# ADC.net
KiCad netlist of a schematic drawn in Altium Designer
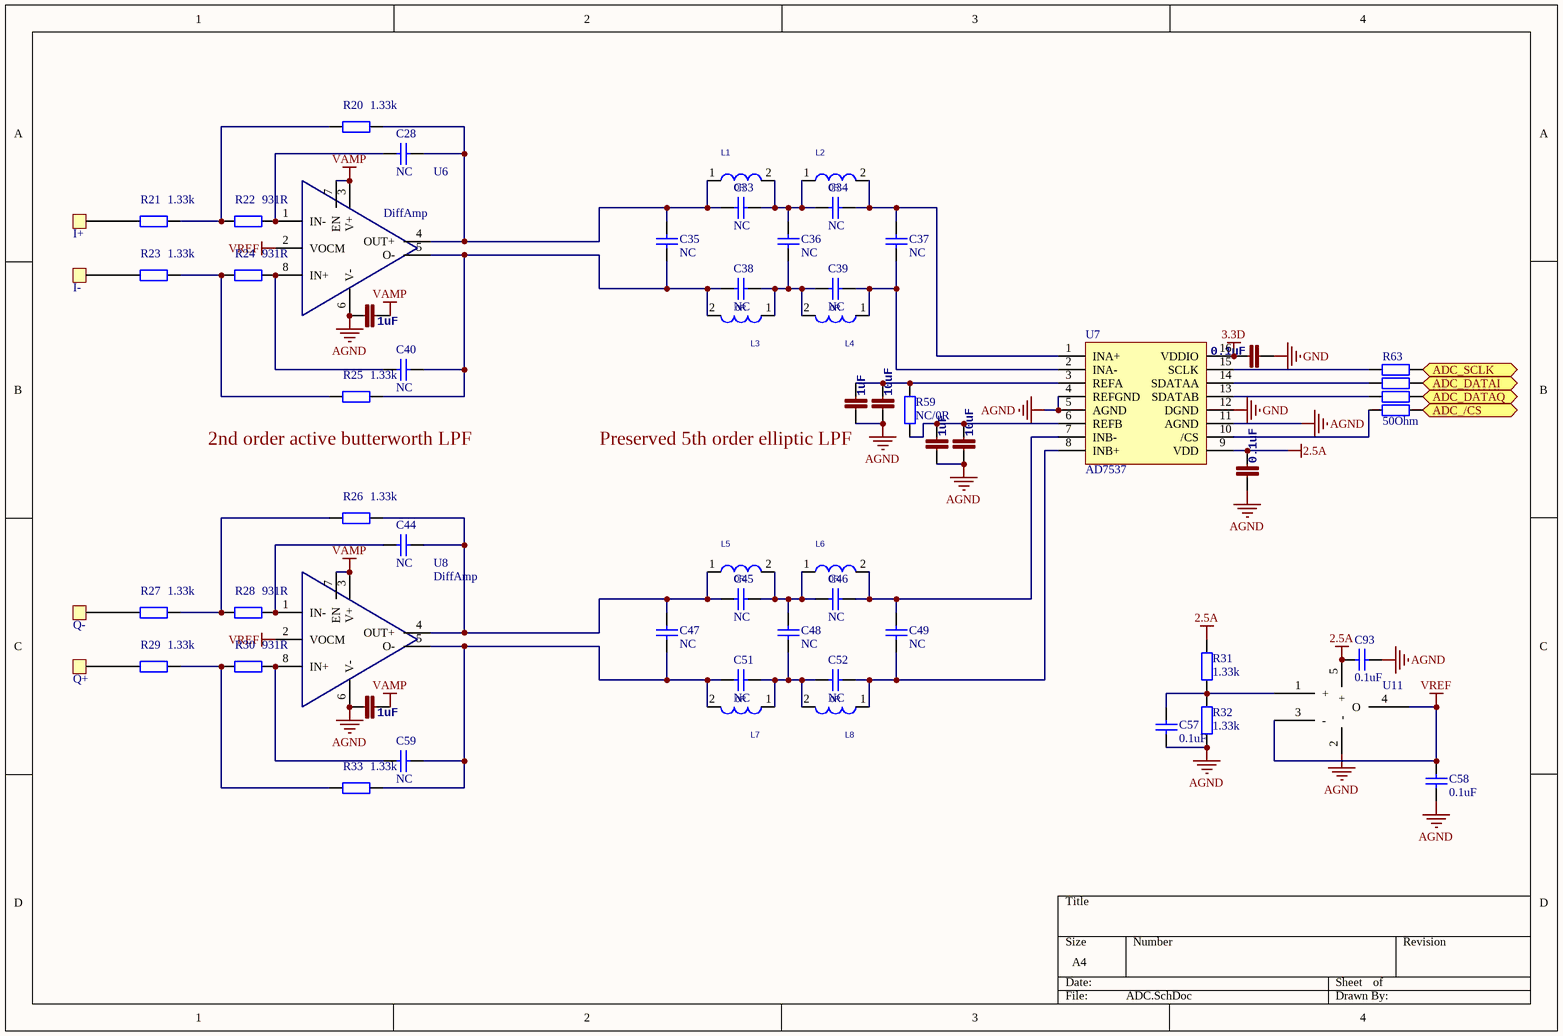
[diagram p0: ADC.SchDoc]

(export (version "E")
  (design (tool "Eeschema 10.0.6"))
  (components
    (comp (ref "C28")
      (value "NC")
      (footprint "0402")
      (description "Capacitor")
      (fields (field (name "PUBLISHER") "Altium Limited"))
      (libsource (lib "RTC6705") (part "Cap"))
    )
    (comp (ref "C29")
      (value "0.1uF")
      (footprint "0402")
      (description "<b>Capacitor</b>\nStandard 0603 ceramic capacitor, and 0.1\" leaded capacitor.")
      (fields (field (name "PARTNO") "CC0402ZRY5V7BB104"))
      (libsource (lib "") (part "CAP0402-CAP_2"))
    )
    (comp (ref "C30")
      (value "0.1uF")
      (footprint "0603")
      (description "<b>Capacitor</b>\nStandard 0603 ceramic capacitor, and 0.1\" leaded capacitor.")
      (fields (field (name "PARTNO") "CC0402ZRY5V7BB104"))
      (libsource (lib "pixhawk2") (part "CAP0402-CAP"))
    )
    (comp (ref "C31")
      (value "10uF")
      (footprint "0603")
      (description "<b>Capacitor</b>\nStandard 0603 ceramic capacitor, and 0.1\" leaded capacitor.")
      (fields (field (name "PARTNO") "CC0402ZRY5V7BB104"))
      (libsource (lib "pixhawk2") (part "CAP0402-CAP"))
    )
    (comp (ref "C32")
      (value "1uF")
      (footprint "0805")
      (description "<b>Capacitor</b>\nStandard 0603 ceramic capacitor, and 0.1\" leaded capacitor.")
      (fields (field (name "PARTNO") "CC0402ZRY5V7BB104"))
      (libsource (lib "pixhawk2") (part "CAP0402-CAP"))
    )
    (comp (ref "C33")
      (value "NC")
      (footprint "0402")
      (description "Capacitor")
      (fields (field (name "PUBLISHER") "Altium Limited"))
      (libsource (lib "RTC6705") (part "Cap"))
    )
    (comp (ref "C34")
      (value "NC")
      (footprint "0402")
      (description "Capacitor")
      (fields (field (name "PUBLISHER") "Altium Limited"))
      (libsource (lib "RTC6705") (part "Cap"))
    )
    (comp (ref "C35")
      (value "NC")
      (footprint "0402")
      (description "Capacitor")
      (fields (field (name "PUBLISHER") "Altium Limited"))
      (libsource (lib "RTC6705") (part "Cap"))
    )
    (comp (ref "C36")
      (value "NC")
      (footprint "0402")
      (description "Capacitor")
      (fields (field (name "PUBLISHER") "Altium Limited"))
      (libsource (lib "RTC6705") (part "Cap"))
    )
    (comp (ref "C37")
      (value "NC")
      (footprint "0402")
      (description "Capacitor")
      (fields (field (name "PUBLISHER") "Altium Limited"))
      (libsource (lib "RTC6705") (part "Cap"))
    )
    (comp (ref "C38")
      (value "NC")
      (footprint "0402")
      (description "Capacitor")
      (fields (field (name "PUBLISHER") "Altium Limited"))
      (libsource (lib "RTC6705") (part "Cap"))
    )
    (comp (ref "C39")
      (value "NC")
      (footprint "0402")
      (description "Capacitor")
      (fields (field (name "PUBLISHER") "Altium Limited"))
      (libsource (lib "RTC6705") (part "Cap"))
    )
    (comp (ref "C40")
      (value "NC")
      (footprint "0402")
      (description "Capacitor")
      (fields (field (name "PUBLISHER") "Altium Limited"))
      (libsource (lib "RTC6705") (part "Cap"))
    )
    (comp (ref "C41")
      (value "1uF")
      (footprint "0603")
      (description "<b>Capacitor</b>\nStandard 0603 ceramic capacitor, and 0.1\" leaded capacitor.")
      (fields (field (name "PARTNO") "CC0402ZRY5V7BB104"))
      (libsource (lib "pixhawk2") (part "CAP0402-CAP"))
    )
    (comp (ref "C43")
      (value "10uF")
      (footprint "0805")
      (description "<b>Capacitor</b>\nStandard 0603 ceramic capacitor, and 0.1\" leaded capacitor.")
      (fields (field (name "PARTNO") "CC0402ZRY5V7BB104"))
      (libsource (lib "pixhawk2") (part "CAP0402-CAP"))
    )
    (comp (ref "C44")
      (value "NC")
      (footprint "0402")
      (description "Capacitor")
      (fields (field (name "PUBLISHER") "Altium Limited"))
      (libsource (lib "RTC6705") (part "Cap"))
    )
    (comp (ref "C45")
      (value "NC")
      (footprint "0402")
      (description "Capacitor")
      (fields (field (name "PUBLISHER") "Altium Limited"))
      (libsource (lib "RTC6705") (part "Cap"))
    )
    (comp (ref "C46")
      (value "NC")
      (footprint "0402")
      (description "Capacitor")
      (fields (field (name "PUBLISHER") "Altium Limited"))
      (libsource (lib "RTC6705") (part "Cap"))
    )
    (comp (ref "C47")
      (value "NC")
      (footprint "0402")
      (description "Capacitor")
      (fields (field (name "PUBLISHER") "Altium Limited"))
      (libsource (lib "RTC6705") (part "Cap"))
    )
    (comp (ref "C48")
      (value "NC")
      (footprint "0402")
      (description "Capacitor")
      (fields (field (name "PUBLISHER") "Altium Limited"))
      (libsource (lib "RTC6705") (part "Cap"))
    )
    (comp (ref "C49")
      (value "NC")
      (footprint "0402")
      (description "Capacitor")
      (fields (field (name "PUBLISHER") "Altium Limited"))
      (libsource (lib "RTC6705") (part "Cap"))
    )
    (comp (ref "C51")
      (value "NC")
      (footprint "0402")
      (description "Capacitor")
      (fields (field (name "PUBLISHER") "Altium Limited"))
      (libsource (lib "RTC6705") (part "Cap"))
    )
    (comp (ref "C52")
      (value "NC")
      (footprint "0402")
      (description "Capacitor")
      (fields (field (name "PUBLISHER") "Altium Limited"))
      (libsource (lib "RTC6705") (part "Cap"))
    )
    (comp (ref "C57")
      (value "0.1uF")
      (footprint "0402")
      (description "Capacitor")
      (fields (field (name "PUBLISHER") "Altium Limited"))
      (libsource (lib "RTC6705") (part "Cap"))
    )
    (comp (ref "C58")
      (value "0.1uF")
      (footprint "0402")
      (description "Capacitor")
      (fields (field (name "PUBLISHER") "Altium Limited"))
      (libsource (lib "RTC6705") (part "Cap"))
    )
    (comp (ref "C59")
      (value "NC")
      (footprint "0402")
      (description "Capacitor")
      (fields (field (name "PUBLISHER") "Altium Limited"))
      (libsource (lib "RTC6705") (part "Cap"))
    )
    (comp (ref "C89")
      (value "1uF")
      (footprint "0603")
      (description "<b>Capacitor</b>\nStandard 0603 ceramic capacitor, and 0.1\" leaded capacitor.")
      (fields (field (name "PARTNO") "CC0402ZRY5V7BB104"))
      (libsource (lib "") (part "CAP0402-CAP_1"))
    )
    (comp (ref "C90")
      (value "1uF")
      (footprint "0603")
      (description "<b>Capacitor</b>\nStandard 0603 ceramic capacitor, and 0.1\" leaded capacitor.")
      (fields (field (name "PARTNO") "CC0402ZRY5V7BB104"))
      (libsource (lib "") (part "CAP0402-CAP_1"))
    )
    (comp (ref "C93")
      (value "0.1uF")
      (footprint "0402")
      (description "Capacitor")
      (fields (field (name "PUBLISHER") "Altium Limited"))
      (libsource (lib "RTC6705") (part "Cap"))
    )
    (comp (ref "I+") (value "TestPad") (footprint "TestPad - 1mm") (libsource (lib "sch") (part "TestPad")))
    (comp (ref "I-") (value "TestPad") (footprint "TestPad - 1mm") (libsource (lib "sch") (part "TestPad")))
    (comp (ref "L1") (value "0R") (footprint "0402") (libsource (lib "*") (part "L/2.5*2.0")))
    (comp (ref "L2") (value "0R") (footprint "0402") (libsource (lib "*") (part "L/2.5*2.0")))
    (comp (ref "L3") (value "0R") (footprint "0402") (libsource (lib "*") (part "L/2.5*2.0")))
    (comp (ref "L4") (value "0R") (footprint "0402") (libsource (lib "*") (part "L/2.5*2.0")))
    (comp (ref "L5") (value "0R") (footprint "0402") (libsource (lib "*") (part "L/2.5*2.0")))
    (comp (ref "L6") (value "0R") (footprint "0402") (libsource (lib "*") (part "L/2.5*2.0")))
    (comp (ref "L7") (value "0R") (footprint "0402") (libsource (lib "*") (part "L/2.5*2.0")))
    (comp (ref "L8") (value "0R") (footprint "0402") (libsource (lib "*") (part "L/2.5*2.0")))
    (comp (ref "Q+") (value "TestPad") (footprint "TestPad - 1mm") (libsource (lib "sch") (part "TestPad")))
    (comp (ref "Q-") (value "TestPad") (footprint "TestPad - 1mm") (libsource (lib "sch") (part "TestPad")))
    (comp (ref "R20")
      (value "1.33k")
      (footprint "0402")
      (description "Resistor")
      (fields (field (name "PUBLISHER") "Altium Limited"))
      (libsource (lib "Miscellaneous Devices") (part "Res2"))
    )
    (comp (ref "R21")
      (value "1.33k")
      (footprint "0402")
      (description "Resistor")
      (fields (field (name "PUBLISHER") "Altium Limited"))
      (libsource (lib "Miscellaneous Devices") (part "Res2"))
    )
    (comp (ref "R22")
      (value "931R")
      (footprint "0402")
      (description "Resistor")
      (fields (field (name "PUBLISHER") "Altium Limited"))
      (libsource (lib "Miscellaneous Devices") (part "Res2"))
    )
    (comp (ref "R23")
      (value "1.33k")
      (footprint "0402")
      (description "Resistor")
      (fields (field (name "PUBLISHER") "Altium Limited"))
      (libsource (lib "Miscellaneous Devices") (part "Res2"))
    )
    (comp (ref "R24")
      (value "931R")
      (footprint "0402")
      (description "Resistor")
      (fields (field (name "PUBLISHER") "Altium Limited"))
      (libsource (lib "Miscellaneous Devices") (part "Res2"))
    )
    (comp (ref "R25")
      (value "1.33k")
      (footprint "0402")
      (description "Resistor")
      (fields (field (name "PUBLISHER") "Altium Limited"))
      (libsource (lib "Miscellaneous Devices") (part "Res2"))
    )
    (comp (ref "R26")
      (value "1.33k")
      (footprint "0402")
      (description "Resistor")
      (fields (field (name "PUBLISHER") "Altium Limited"))
      (libsource (lib "Miscellaneous Devices") (part "Res2"))
    )
    (comp (ref "R27")
      (value "1.33k")
      (footprint "0402")
      (description "Resistor")
      (fields (field (name "PUBLISHER") "Altium Limited"))
      (libsource (lib "Miscellaneous Devices") (part "Res2"))
    )
    (comp (ref "R28")
      (value "931R")
      (footprint "0402")
      (description "Resistor")
      (fields (field (name "PUBLISHER") "Altium Limited"))
      (libsource (lib "Miscellaneous Devices") (part "Res2"))
    )
    (comp (ref "R29")
      (value "1.33k")
      (footprint "0402")
      (description "Resistor")
      (fields (field (name "PUBLISHER") "Altium Limited"))
      (libsource (lib "Miscellaneous Devices") (part "Res2"))
    )
    (comp (ref "R30")
      (value "931R")
      (footprint "0402")
      (description "Resistor")
      (fields (field (name "PUBLISHER") "Altium Limited"))
      (libsource (lib "Miscellaneous Devices") (part "Res2"))
    )
    (comp (ref "R31")
      (value "1.33k")
      (footprint "0402")
      (description "Resistor")
      (fields (field (name "PUBLISHER") "Altium Limited"))
      (libsource (lib "") (part "Res2_1"))
    )
    (comp (ref "R32")
      (value "1.33k")
      (footprint "0402")
      (description "Resistor")
      (fields (field (name "PUBLISHER") "Altium Limited"))
      (libsource (lib "") (part "Res2_1"))
    )
    (comp (ref "R33")
      (value "1.33k")
      (footprint "0402")
      (description "Resistor")
      (fields (field (name "PUBLISHER") "Altium Limited"))
      (libsource (lib "Miscellaneous Devices") (part "Res2"))
    )
    (comp (ref "R59")
      (value "NC/0R")
      (footprint "0402")
      (description "Resistor")
      (fields (field (name "PUBLISHER") "Altium Limited"))
      (libsource (lib "") (part "Res2_2"))
    )
    (comp (ref "R63")
      (value "50Ohm")
      (footprint "0402X4")
      (description "Resistor")
      (fields (field (name "Comment") "Res*4") (field (name "PUBLISHER") "Altium Limited"))
      (libsource (lib "sch") (part "Res*4"))
    )
    (comp (ref "U6") (value "DiffAmp") (footprint "MSOP8/VSSOP8") (libsource (lib "F4SDR") (part "DiffAmp")))
    (comp (ref "U7") (value "AD7537") (footprint "AD7357") (libsource (lib "F4SDR") (part "AD7537")))
    (comp (ref "U8") (value "DiffAmp") (footprint "MSOP8/VSSOP8") (libsource (lib "F4SDR") (part "DiffAmp")))
    (comp (ref "U11") (value "OP-SOT23") (footprint "SOT23-5") (libsource (lib "sch") (part "OP-SOT23")))
  )
  (nets
    (net (code "1") (name "/ADC_DATAI") (class "Default")
      (node (ref "R63") (pin "3") (pinfunction "3_3") (pintype "passive"))
    )
    (net (code "2") (name "/ADC_DATAQ") (class "Default")
      (node (ref "R63") (pin "2") (pinfunction "2_2") (pintype "passive"))
    )
    (net (code "3") (name "/ADC_SCLK") (class "Default")
      (node (ref "R63") (pin "4") (pinfunction "4_4") (pintype "passive"))
    )
    (net (code "4") (name "/ADC_{slash}CS") (class "Default")
      (node (ref "R63") (pin "1") (pinfunction "1_1") (pintype "passive"))
    )
    (net (code "5") (name "2.5A") (class "Default")
      (node (ref "C30") (pin "1") (pinfunction "1_1") (pintype "passive"))
      (node (ref "C93") (pin "1") (pinfunction "1_1") (pintype "passive"))
      (node (ref "R31") (pin "1") (pinfunction "1_1") (pintype "passive"))
      (node (ref "U11") (pin "5") (pinfunction "+_5") (pintype "passive"))
      (node (ref "U7") (pin "9") (pinfunction "VDD_9") (pintype "passive"))
    )
    (net (code "6") (name "3.3D") (class "Default")
      (node (ref "C29") (pin "1") (pinfunction "1_1") (pintype "passive"))
      (node (ref "U7") (pin "16") (pinfunction "VDDIO_16") (pintype "passive"))
    )
    (net (code "7") (name "AGND") (class "Default")
      (node (ref "C30") (pin "2") (pinfunction "2_2") (pintype "passive"))
      (node (ref "C31") (pin "2") (pinfunction "2_2") (pintype "passive"))
      (node (ref "C32") (pin "2") (pinfunction "2_2") (pintype "passive"))
      (node (ref "C41") (pin "2") (pinfunction "2_2") (pintype "passive"))
      (node (ref "C43") (pin "2") (pinfunction "2_2") (pintype "passive"))
      (node (ref "C57") (pin "2") (pinfunction "2_2") (pintype "passive"))
      (node (ref "C58") (pin "2") (pinfunction "2_2") (pintype "passive"))
      (node (ref "C89") (pin "2") (pinfunction "2_2") (pintype "passive"))
      (node (ref "C90") (pin "2") (pinfunction "2_2") (pintype "passive"))
      (node (ref "C93") (pin "2") (pinfunction "2_2") (pintype "passive"))
      (node (ref "R32") (pin "2") (pinfunction "2_2") (pintype "passive"))
      (node (ref "U11") (pin "2") (pinfunction "-_2") (pintype "passive"))
      (node (ref "U6") (pin "6") (pinfunction "V-_6") (pintype "passive"))
      (node (ref "U7") (pin "11") (pinfunction "AGND_11") (pintype "passive"))
      (node (ref "U7") (pin "4") (pinfunction "REFGND_4") (pintype "passive"))
      (node (ref "U7") (pin "5") (pinfunction "AGND_5") (pintype "passive"))
      (node (ref "U8") (pin "6") (pinfunction "V-_6") (pintype "passive"))
    )
    (net (code "8") (name "GND") (class "Default")
      (node (ref "C29") (pin "2") (pinfunction "2_2") (pintype "passive"))
      (node (ref "U7") (pin "12") (pinfunction "DGND_12") (pintype "passive"))
    )
    (net (code "9") (name "Net-(C33-Pad1)") (class "Default")
      (node (ref "C33") (pin "1") (pinfunction "1_1") (pintype "passive"))
      (node (ref "C34") (pin "2") (pinfunction "2_2") (pintype "passive"))
      (node (ref "C36") (pin "2") (pinfunction "2_2") (pintype "passive"))
      (node (ref "L1") (pin "2") (pinfunction "2_2") (pintype "passive"))
      (node (ref "L2") (pin "1") (pinfunction "1_1") (pintype "passive"))
    )
    (net (code "10") (name "Net-(C36-Pad1)") (class "Default")
      (node (ref "C36") (pin "1") (pinfunction "1_1") (pintype "passive"))
      (node (ref "C38") (pin "2") (pinfunction "2_2") (pintype "passive"))
      (node (ref "C39") (pin "1") (pinfunction "1_1") (pintype "passive"))
      (node (ref "L3") (pin "1") (pinfunction "1_1") (pintype "passive"))
      (node (ref "L4") (pin "2") (pinfunction "2_2") (pintype "passive"))
    )
    (net (code "11") (name "Net-(C45-Pad1)") (class "Default")
      (node (ref "C45") (pin "1") (pinfunction "1_1") (pintype "passive"))
      (node (ref "C46") (pin "2") (pinfunction "2_2") (pintype "passive"))
      (node (ref "C48") (pin "2") (pinfunction "2_2") (pintype "passive"))
      (node (ref "L5") (pin "2") (pinfunction "2_2") (pintype "passive"))
      (node (ref "L6") (pin "1") (pinfunction "1_1") (pintype "passive"))
    )
    (net (code "12") (name "Net-(C48-Pad1)") (class "Default")
      (node (ref "C48") (pin "1") (pinfunction "1_1") (pintype "passive"))
      (node (ref "C51") (pin "2") (pinfunction "2_2") (pintype "passive"))
      (node (ref "C52") (pin "1") (pinfunction "1_1") (pintype "passive"))
      (node (ref "L7") (pin "1") (pinfunction "1_1") (pintype "passive"))
      (node (ref "L8") (pin "2") (pinfunction "2_2") (pintype "passive"))
    )
    (net (code "13") (name "Net-(C57-Pad1)") (class "Default")
      (node (ref "C57") (pin "1") (pinfunction "1_1") (pintype "passive"))
      (node (ref "R31") (pin "2") (pinfunction "2_2") (pintype "passive"))
      (node (ref "R32") (pin "1") (pinfunction "1_1") (pintype "passive"))
      (node (ref "U11") (pin "1") (pinfunction "+_1") (pintype "passive"))
    )
    (net (code "14") (name "Net-(I+-3)") (class "Default")
      (node (ref "I+") (pin "1") (pinfunction "3_1") (pintype "passive"))
      (node (ref "R21") (pin "2") (pinfunction "2_2") (pintype "passive"))
    )
    (net (code "15") (name "Net-(I--3)") (class "Default")
      (node (ref "I-") (pin "1") (pinfunction "3_1") (pintype "passive"))
      (node (ref "R23") (pin "2") (pinfunction "2_2") (pintype "passive"))
    )
    (net (code "16") (name "Net-(Q+-3)") (class "Default")
      (node (ref "Q+") (pin "1") (pinfunction "3_1") (pintype "passive"))
      (node (ref "R29") (pin "2") (pinfunction "2_2") (pintype "passive"))
    )
    (net (code "17") (name "Net-(Q--3)") (class "Default")
      (node (ref "Q-") (pin "1") (pinfunction "3_1") (pintype "passive"))
      (node (ref "R27") (pin "2") (pinfunction "2_2") (pintype "passive"))
    )
    (net (code "18") (name "Net-(R20-Pad2)") (class "Default")
      (node (ref "R20") (pin "2") (pinfunction "2_2") (pintype "passive"))
      (node (ref "R21") (pin "1") (pinfunction "1_1") (pintype "passive"))
      (node (ref "R22") (pin "2") (pinfunction "2_2") (pintype "passive"))
    )
    (net (code "19") (name "Net-(R23-Pad1)") (class "Default")
      (node (ref "R23") (pin "1") (pinfunction "1_1") (pintype "passive"))
      (node (ref "R24") (pin "2") (pinfunction "2_2") (pintype "passive"))
      (node (ref "R25") (pin "2") (pinfunction "2_2") (pintype "passive"))
    )
    (net (code "20") (name "Net-(R26-Pad2)") (class "Default")
      (node (ref "R26") (pin "2") (pinfunction "2_2") (pintype "passive"))
      (node (ref "R27") (pin "1") (pinfunction "1_1") (pintype "passive"))
      (node (ref "R28") (pin "2") (pinfunction "2_2") (pintype "passive"))
    )
    (net (code "21") (name "Net-(R29-Pad1)") (class "Default")
      (node (ref "R29") (pin "1") (pinfunction "1_1") (pintype "passive"))
      (node (ref "R30") (pin "2") (pinfunction "2_2") (pintype "passive"))
      (node (ref "R33") (pin "2") (pinfunction "2_2") (pintype "passive"))
    )
    (net (code "22") (name "Net-(U6-IN+)") (class "Default")
      (node (ref "C40") (pin "2") (pinfunction "2_2") (pintype "passive"))
      (node (ref "R24") (pin "1") (pinfunction "1_1") (pintype "passive"))
      (node (ref "U6") (pin "8") (pinfunction "IN+_8") (pintype "passive"))
    )
    (net (code "23") (name "Net-(U6-IN-)") (class "Default")
      (node (ref "C28") (pin "2") (pinfunction "2_2") (pintype "passive"))
      (node (ref "R22") (pin "1") (pinfunction "1_1") (pintype "passive"))
      (node (ref "U6") (pin "1") (pinfunction "IN-_1") (pintype "passive"))
    )
    (net (code "24") (name "Net-(U6-O-)") (class "Default")
      (node (ref "C35") (pin "1") (pinfunction "1_1") (pintype "passive"))
      (node (ref "C38") (pin "1") (pinfunction "1_1") (pintype "passive"))
      (node (ref "C40") (pin "1") (pinfunction "1_1") (pintype "passive"))
      (node (ref "L3") (pin "2") (pinfunction "2_2") (pintype "passive"))
      (node (ref "R25") (pin "1") (pinfunction "1_1") (pintype "passive"))
      (node (ref "U6") (pin "5") (pinfunction "O-_5") (pintype "passive"))
    )
    (net (code "25") (name "Net-(U6-OUT+)") (class "Default")
      (node (ref "C28") (pin "1") (pinfunction "1_1") (pintype "passive"))
      (node (ref "C33") (pin "2") (pinfunction "2_2") (pintype "passive"))
      (node (ref "C35") (pin "2") (pinfunction "2_2") (pintype "passive"))
      (node (ref "L1") (pin "1") (pinfunction "1_1") (pintype "passive"))
      (node (ref "R20") (pin "1") (pinfunction "1_1") (pintype "passive"))
      (node (ref "U6") (pin "4") (pinfunction "OUT+_4") (pintype "passive"))
    )
    (net (code "26") (name "Net-(U7-INA+)") (class "Default")
      (node (ref "C34") (pin "1") (pinfunction "1_1") (pintype "passive"))
      (node (ref "C37") (pin "2") (pinfunction "2_2") (pintype "passive"))
      (node (ref "L2") (pin "2") (pinfunction "2_2") (pintype "passive"))
      (node (ref "U7") (pin "1") (pinfunction "INA+_1") (pintype "passive"))
    )
    (net (code "27") (name "Net-(U7-INA-)") (class "Default")
      (node (ref "C37") (pin "1") (pinfunction "1_1") (pintype "passive"))
      (node (ref "C39") (pin "2") (pinfunction "2_2") (pintype "passive"))
      (node (ref "L4") (pin "1") (pinfunction "1_1") (pintype "passive"))
      (node (ref "U7") (pin "2") (pinfunction "INA-_2") (pintype "passive"))
    )
    (net (code "28") (name "Net-(U7-INB+)") (class "Default")
      (node (ref "C49") (pin "1") (pinfunction "1_1") (pintype "passive"))
      (node (ref "C52") (pin "2") (pinfunction "2_2") (pintype "passive"))
      (node (ref "L8") (pin "1") (pinfunction "1_1") (pintype "passive"))
      (node (ref "U7") (pin "8") (pinfunction "INB+_8") (pintype "passive"))
    )
    (net (code "29") (name "Net-(U7-INB-)") (class "Default")
      (node (ref "C46") (pin "1") (pinfunction "1_1") (pintype "passive"))
      (node (ref "C49") (pin "2") (pinfunction "2_2") (pintype "passive"))
      (node (ref "L6") (pin "2") (pinfunction "2_2") (pintype "passive"))
      (node (ref "U7") (pin "7") (pinfunction "INB-_7") (pintype "passive"))
    )
    (net (code "30") (name "Net-(U7-REFA)") (class "Default")
      (node (ref "C41") (pin "1") (pinfunction "1_1") (pintype "passive"))
      (node (ref "C43") (pin "1") (pinfunction "1_1") (pintype "passive"))
      (node (ref "R59") (pin "2") (pinfunction "2_2") (pintype "passive"))
      (node (ref "U7") (pin "3") (pinfunction "REFA_3") (pintype "passive"))
    )
    (net (code "31") (name "Net-(U7-REFB)") (class "Default")
      (node (ref "C31") (pin "1") (pinfunction "1_1") (pintype "passive"))
      (node (ref "C32") (pin "1") (pinfunction "1_1") (pintype "passive"))
      (node (ref "R59") (pin "1") (pinfunction "1_1") (pintype "passive"))
      (node (ref "U7") (pin "6") (pinfunction "REFB_6") (pintype "passive"))
    )
    (net (code "32") (name "Net-(U7-SCLK)") (class "Default")
      (node (ref "R63") (pin "5") (pinfunction "5_5") (pintype "passive"))
      (node (ref "U7") (pin "15") (pinfunction "SCLK_15") (pintype "passive"))
    )
    (net (code "33") (name "Net-(U7-SDATAA)") (class "Default")
      (node (ref "R63") (pin "6") (pinfunction "6_6") (pintype "passive"))
      (node (ref "U7") (pin "14") (pinfunction "SDATAA_14") (pintype "passive"))
    )
    (net (code "34") (name "Net-(U7-SDATAB)") (class "Default")
      (node (ref "R63") (pin "7") (pinfunction "7_7") (pintype "passive"))
      (node (ref "U7") (pin "13") (pinfunction "SDATAB_13") (pintype "passive"))
    )
    (net (code "35") (name "Net-(U7-{slash}CS)") (class "Default")
      (node (ref "R63") (pin "8") (pinfunction "8_8") (pintype "passive"))
      (node (ref "U7") (pin "10") (pinfunction "/CS_10") (pintype "passive"))
    )
    (net (code "36") (name "Net-(U8-IN+)") (class "Default")
      (node (ref "C59") (pin "2") (pinfunction "2_2") (pintype "passive"))
      (node (ref "R30") (pin "1") (pinfunction "1_1") (pintype "passive"))
      (node (ref "U8") (pin "8") (pinfunction "IN+_8") (pintype "passive"))
    )
    (net (code "37") (name "Net-(U8-IN-)") (class "Default")
      (node (ref "C44") (pin "2") (pinfunction "2_2") (pintype "passive"))
      (node (ref "R28") (pin "1") (pinfunction "1_1") (pintype "passive"))
      (node (ref "U8") (pin "1") (pinfunction "IN-_1") (pintype "passive"))
    )
    (net (code "38") (name "Net-(U8-O-)") (class "Default")
      (node (ref "C47") (pin "1") (pinfunction "1_1") (pintype "passive"))
      (node (ref "C51") (pin "1") (pinfunction "1_1") (pintype "passive"))
      (node (ref "C59") (pin "1") (pinfunction "1_1") (pintype "passive"))
      (node (ref "L7") (pin "2") (pinfunction "2_2") (pintype "passive"))
      (node (ref "R33") (pin "1") (pinfunction "1_1") (pintype "passive"))
      (node (ref "U8") (pin "5") (pinfunction "O-_5") (pintype "passive"))
    )
    (net (code "39") (name "Net-(U8-OUT+)") (class "Default")
      (node (ref "C44") (pin "1") (pinfunction "1_1") (pintype "passive"))
      (node (ref "C45") (pin "2") (pinfunction "2_2") (pintype "passive"))
      (node (ref "C47") (pin "2") (pinfunction "2_2") (pintype "passive"))
      (node (ref "L5") (pin "1") (pinfunction "1_1") (pintype "passive"))
      (node (ref "R26") (pin "1") (pinfunction "1_1") (pintype "passive"))
      (node (ref "U8") (pin "4") (pinfunction "OUT+_4") (pintype "passive"))
    )
    (net (code "40") (name "VAMP") (class "Default")
      (node (ref "C89") (pin "1") (pinfunction "1_1") (pintype "passive"))
      (node (ref "C90") (pin "1") (pinfunction "1_1") (pintype "passive"))
      (node (ref "U6") (pin "3") (pinfunction "V+_3") (pintype "passive"))
      (node (ref "U6") (pin "7") (pinfunction "EN_7") (pintype "passive"))
      (node (ref "U8") (pin "3") (pinfunction "V+_3") (pintype "passive"))
      (node (ref "U8") (pin "7") (pinfunction "EN_7") (pintype "passive"))
    )
    (net (code "41") (name "VREF") (class "Default")
      (node (ref "C58") (pin "1") (pinfunction "1_1") (pintype "passive"))
      (node (ref "U11") (pin "3") (pinfunction "-_3") (pintype "passive"))
      (node (ref "U11") (pin "4") (pinfunction "O_4") (pintype "passive"))
      (node (ref "U6") (pin "2") (pinfunction "VOCM_2") (pintype "passive"))
      (node (ref "U8") (pin "2") (pinfunction "VOCM_2") (pintype "passive"))
    )
  )
)
